# PowerBoard.net
KiCad netlist of a schematic drawn in Altium Designer
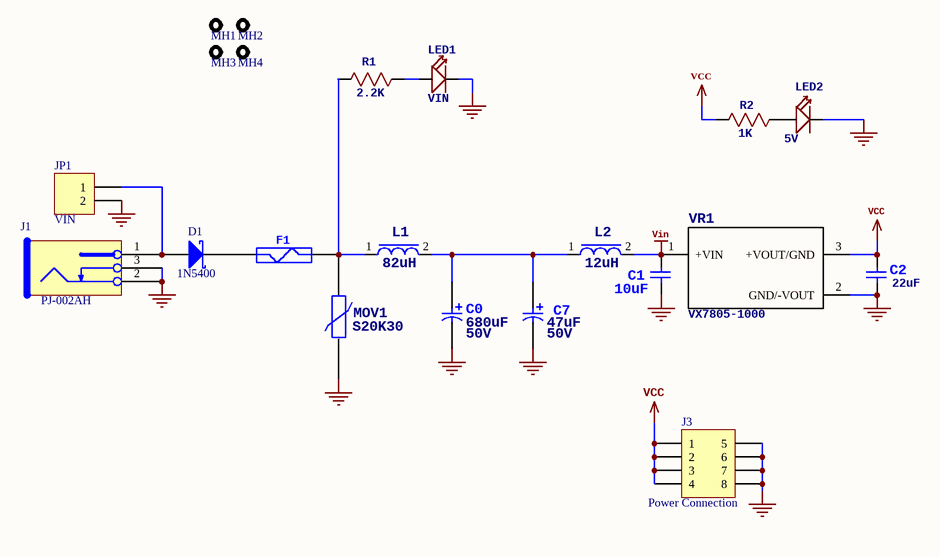
[diagram p0: PowerBoard.SchDoc]

(export (version "E")
  (design (tool "Eeschema 10.0.6"))
  (components
    (comp (ref "C0")
      (value "680uF")
      (footprint "PCBComponent_1")
      (description "CAP_UC_30D")
      (fields (field (name "VOLTAGE") "50V") (field (name "Comment") "CAP_UC"))
      (libsource (lib "AltiumIntegratedLibrary") (part "CAP_UC"))
    )
    (comp (ref "C1")
      (value "10uF")
      (footprint "RES_0805")
      (description "0805 SMD Ceramic Cap")
      (libsource (lib "AltiumIntegratedLibrary") (part "CAP_0805"))
    )
    (comp (ref "C2")
      (value "22uF")
      (footprint "RES_0805")
      (description "0805 SMD Ceramic Cap")
      (libsource (lib "AltiumIntegratedLibrary") (part "CAP_0805"))
    )
    (comp (ref "C7")
      (value "47uF")
      (footprint "PCBComponent_1")
      (description "CAP_UC_30D")
      (fields (field (name "VOLTAGE") "50V"))
      (libsource (lib "AltiumIntegratedLibrary") (part "CAP_UC"))
    )
    (comp (ref "D1")
      (value "1N5400")
      (footprint "DO-214AC")
      (description "Schottky Diode")
      (fields (field (name "PUBLISHER") "Altium Limited"))
      (libsource (lib "105848_revD3") (part "D Schottky"))
    )
    (comp (ref "F1")
      (value "FUSE_5MM")
      (footprint "FUSE_5MM")
      (libsource (lib "AltiumIntegratedLibrary") (part "FUSE_5MM"))
    )
    (comp (ref "J1")
      (value "PJ-002AH")
      (footprint "POWER_JACK_5.5_2.1MM_NS")
      (description "CONN PWR JACK 2.1X5.5MM HIGH CUR")
      (fields (field (name "MANUFACTURER") "CUI Inc"))
      (libsource (lib "iMX6 Rex Development Baseboard V1I1") (part "PJ-002AH"))
    )
    (comp (ref "J3")
      (value "Power Connection")
      (footprint "HDR2X4_CEN")
      (description "Header, 4-Pin, Dual row")
      (fields (field (name "PUBLISHER") "Altium Limited"))
      (libsource (lib "Miscellaneous Connectors") (part "Header 4X2A"))
    )
    (comp (ref "JP1")
      (value "VIN")
      (footprint "HDR1X2")
      (description "Header, 2-Pin")
      (fields (field (name "PUBLISHER") "Altium Limited"))
      (libsource (lib "Miscellaneous Connectors") (part "Header 2"))
    )
    (comp (ref "L1")
      (value "82uH")
      (footprint "CODACA_CSAB0630-100M_0")
      (fields (field (name "PART NUMBER") "CSAB0630-100M"))
      (libsource (lib "Ind_CODACA_CSAB0630-100M_eec") (part "CSAB0630-100M"))
    )
    (comp (ref "L2")
      (value "12uH")
      (footprint "INDUCTOR")
      (fields (field (name "PART NUMBER") "CSAB0630-100M"))
      (libsource (lib "Ind_CODACA_CSAB0630-100M_eec") (part "CSAB0630-100M"))
    )
    (comp (ref "LED1")
      (value "VIN")
      (footprint "LED-0805")
      (fields (field (name "MPN") "17-215SURC/S530-A2/TR8"))
      (libsource (lib "105848_revD3") (part "SMD-LED-CLEAR-RED(0805)"))
    )
    (comp (ref "LED2")
      (value "5V")
      (footprint "LED-0805")
      (fields (field (name "MPN") "17-215SURC/S530-A2/TR8"))
      (libsource (lib "105848_revD3") (part "SMD-LED-CLEAR-RED(0805)"))
    )
    (comp (ref "MH1")
      (value "Mounting Hole")
      (footprint "Mounting-Hole-RND-Altium")
      (libsource (lib "ECS-153-20-4X") (part "Mounting Hole"))
    )
    (comp (ref "MH2")
      (value "Mounting Hole")
      (footprint "Mounting-Hole-RND-Altium")
      (libsource (lib "ECS-153-20-4X") (part "Mounting Hole"))
    )
    (comp (ref "MH3")
      (value "Mounting Hole")
      (footprint "Mounting-Hole-RND-Altium")
      (libsource (lib "ECS-153-20-4X") (part "Mounting Hole"))
    )
    (comp (ref "MH4")
      (value "Mounting Hole")
      (footprint "Mounting-Hole-RND-Altium")
      (libsource (lib "ECS-153-20-4X") (part "Mounting Hole"))
    )
    (comp (ref "MOV1")
      (value "MOV_7MM")
      (footprint "MOV_7MM")
      (fields (field (name "MFR P/N") "S20K30"))
      (libsource (lib "AltiumIntegratedLibrary") (part "MOV_7MM"))
    )
    (comp (ref "R1")
      (value "2.2K")
      (footprint "RESC0805(2012)_M")
      (fields (field (name "MPN") "MCPWR05FTEW2005") (field (name "TOLERANCE") "± 1%"))
      (libsource (lib "Multicomp_By_element14_Batch_1") (part "MCPWR05FTEW2005"))
    )
    (comp (ref "R2")
      (value "1K")
      (footprint "RESC0805(2012)_M")
      (fields (field (name "MPN") "MCPWR05FTEW2005") (field (name "TOLERANCE") "± 1%"))
      (libsource (lib "Multicomp_By_element14_Batch_1") (part "MCPWR05FTEW2005"))
    )
    (comp (ref "VR1")
      (value "VX7805-1000")
      (footprint "VX7805-1000")
      (description "1 A Output Current, 6~36 Vdc Input, 3 Pin SIP, Non-Isolated, Dc-Dc Converter")
      (fields (field (name "MF") "CUI Inc.") (field (name "DIGI-KEY_PART_NUMBER") "102-4253-ND"))
      (libsource (lib "VX7805-1000") (part "VX7805-1000"))
    )
  )
  (nets
    (net (code "1") (name "GND") (class "Default")
      (node (ref "C0") (pin "2") (pinfunction "MINUS_2") (pintype "passive"))
      (node (ref "C1") (pin "2") (pintype "passive"))
      (node (ref "C2") (pin "2") (pintype "passive"))
      (node (ref "C7") (pin "2") (pinfunction "MINUS_2") (pintype "passive"))
      (node (ref "J1") (pin "2") (pinfunction "2_2") (pintype "passive"))
      (node (ref "J1") (pin "3") (pinfunction "3_3") (pintype "passive"))
      (node (ref "J3") (pin "5") (pinfunction "5_5") (pintype "passive"))
      (node (ref "J3") (pin "6") (pinfunction "6_6") (pintype "passive"))
      (node (ref "J3") (pin "7") (pinfunction "7_7") (pintype "passive"))
      (node (ref "J3") (pin "8") (pinfunction "8_8") (pintype "passive"))
      (node (ref "JP1") (pin "2") (pinfunction "2_2") (pintype "passive"))
      (node (ref "LED1") (pin "-") (pinfunction "-_-") (pintype "passive"))
      (node (ref "LED2") (pin "-") (pinfunction "-_-") (pintype "passive"))
      (node (ref "MOV1") (pin "2") (pintype "passive"))
      (node (ref "VR1") (pin "2") (pinfunction "GND/-VOUT_2") (pintype "power_in"))
    )
    (net (code "2") (name "Net-(C0-PLUS)") (class "Default")
      (node (ref "C0") (pin "1") (pinfunction "PLUS_1") (pintype "passive"))
      (node (ref "C7") (pin "1") (pinfunction "PLUS_1") (pintype "passive"))
      (node (ref "L1") (pin "2") (pinfunction "2_2") (pintype "passive"))
      (node (ref "L2") (pin "1") (pinfunction "1_1") (pintype "passive"))
    )
    (net (code "3") (name "Net-(D1-A)") (class "Default")
      (node (ref "D1") (pin "1") (pinfunction "A_1") (pintype "passive"))
      (node (ref "J1") (pin "1") (pinfunction "1_1") (pintype "passive"))
      (node (ref "JP1") (pin "1") (pinfunction "1_1") (pintype "passive"))
    )
    (net (code "4") (name "Net-(D1-K)") (class "Default")
      (node (ref "D1") (pin "2") (pinfunction "K_2") (pintype "passive"))
      (node (ref "F1") (pin "1") (pinfunction "1_1") (pintype "passive"))
    )
    (net (code "5") (name "Net-(R1-R1)") (class "Default")
      (node (ref "LED1") (pin "+") (pinfunction "+_+") (pintype "passive"))
      (node (ref "R1") (pin "1") (pinfunction "R1_1") (pintype "passive"))
    )
    (net (code "6") (name "Net-(R1-R2)") (class "Default")
      (node (ref "F1") (pin "2") (pinfunction "2_2") (pintype "passive"))
      (node (ref "L1") (pin "1") (pinfunction "1_1") (pintype "passive"))
      (node (ref "MOV1") (pin "1") (pintype "passive"))
      (node (ref "R1") (pin "2") (pinfunction "R2_2") (pintype "passive"))
    )
    (net (code "7") (name "Net-(R2-R1)") (class "Default")
      (node (ref "LED2") (pin "+") (pinfunction "+_+") (pintype "passive"))
      (node (ref "R2") (pin "1") (pinfunction "R1_1") (pintype "passive"))
    )
    (net (code "8") (name "VCC") (class "Default")
      (node (ref "C2") (pin "1") (pintype "passive"))
      (node (ref "J3") (pin "1") (pinfunction "1_1") (pintype "passive"))
      (node (ref "J3") (pin "2") (pinfunction "2_2") (pintype "passive"))
      (node (ref "J3") (pin "3") (pinfunction "3_3") (pintype "passive"))
      (node (ref "J3") (pin "4") (pinfunction "4_4") (pintype "passive"))
      (node (ref "R2") (pin "2") (pinfunction "R2_2") (pintype "passive"))
      (node (ref "VR1") (pin "3") (pinfunction "+VOUT/GND_3") (pintype "power_in"))
    )
    (net (code "9") (name "Vin") (class "Default")
      (node (ref "C1") (pin "1") (pintype "passive"))
      (node (ref "L2") (pin "2") (pinfunction "2_2") (pintype "passive"))
      (node (ref "VR1") (pin "1") (pinfunction "+VIN_1") (pintype "power_in"))
    )
  )
)
